# cc2538.net
KiCad netlist of a schematic drawn in Altium Designer
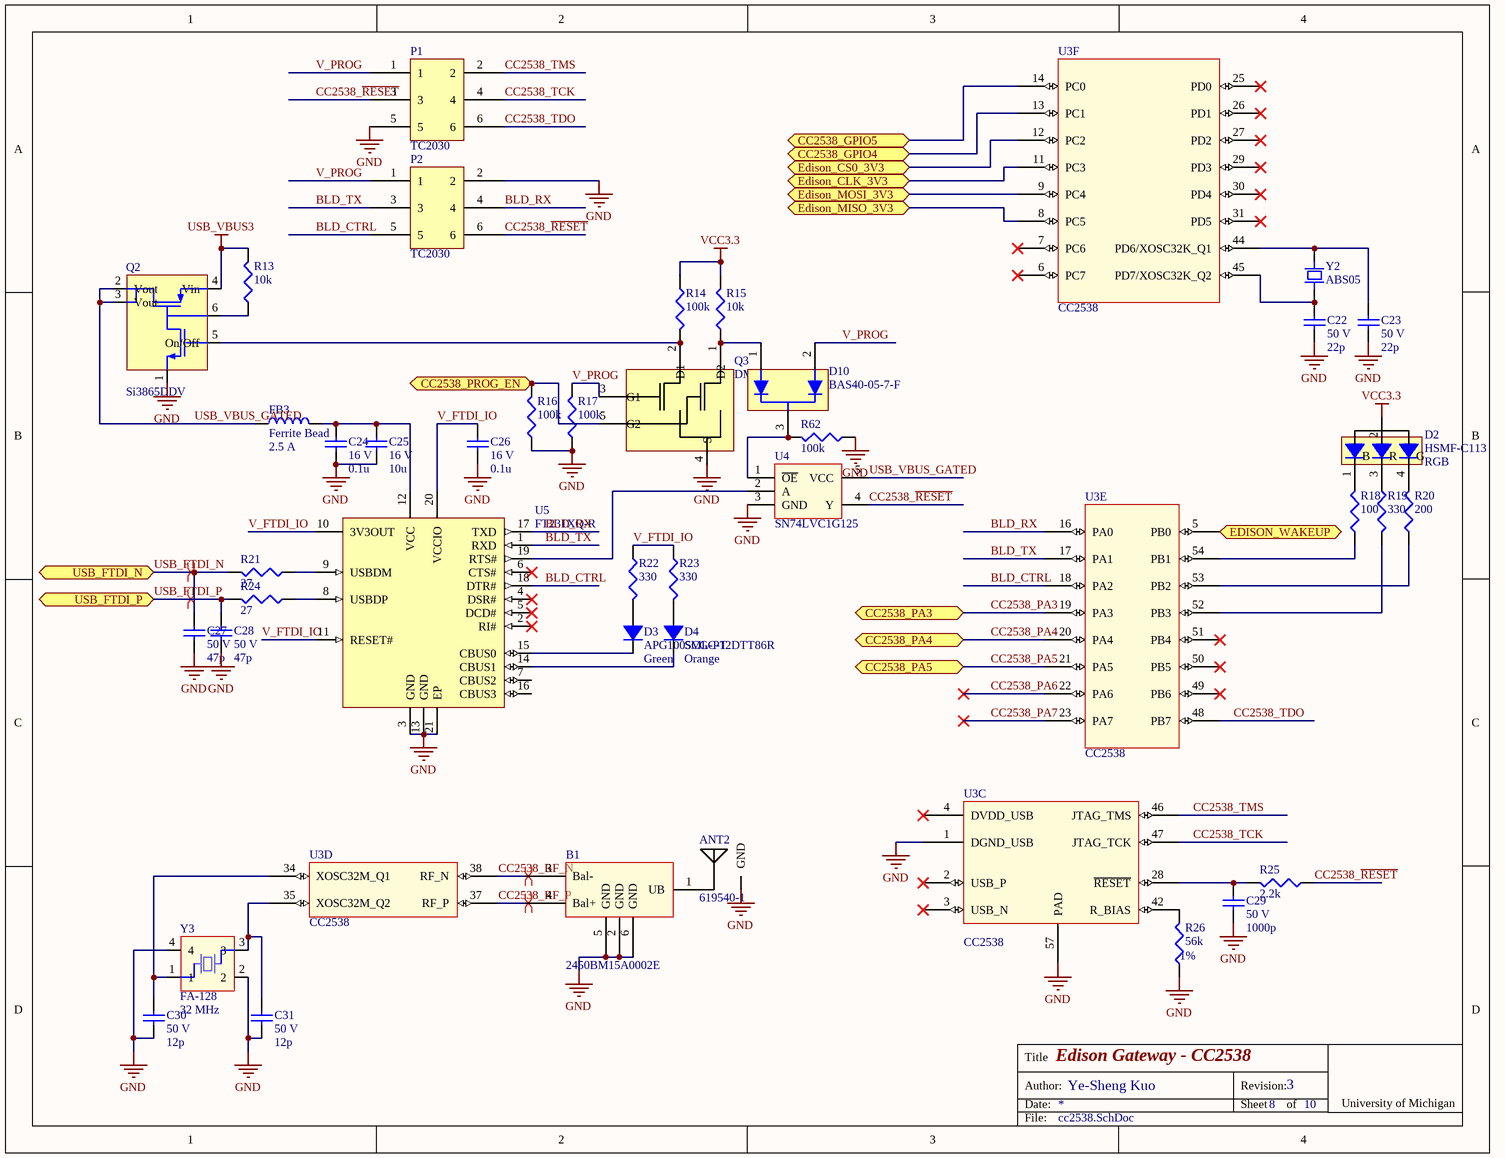
[diagram p0: cc2538.SchDoc]

(export (version "E")
  (design (tool "Eeschema 10.0.6"))
  (components
    (comp (ref "ANT2")
      (value "619540-1")
      (footprint "619540-1")
      (description "CONN SMA JACK")
      (libsource (lib "RF") (part "619540-1"))
    )
    (comp (ref "B1")
      (value "2450BM15A0002E")
      (footprint "2450BM15A0002")
      (description "2.45 GHz Balun for TI CC253X")
      (libsource (lib "RF") (part "2450BM15A0002E"))
    )
    (comp (ref "C22")
      (value "22p")
      (footprint "0402")
      (description "22pF ±2% 50V Ceramic Capacitor C0G, NP0 0402")
      (fields
        (field (name "VOLTAGE RATED") "50 V")
        (field (name "TOLERANCE") "2%")
        (field (name "MANUFACTURER PART NUMBER") "500R07S220GV4T")
      )
      (libsource (lib "capacitors") (part "500R07S220GV4T"))
    )
    (comp (ref "C23")
      (value "22p")
      (footprint "0402")
      (description "22pF ±2% 50V Ceramic Capacitor C0G, NP0 0402")
      (fields
        (field (name "VOLTAGE RATED") "50 V")
        (field (name "TOLERANCE") "2%")
        (field (name "MANUFACTURER PART NUMBER") "500R07S220GV4T")
      )
      (libsource (lib "capacitors") (part "500R07S220GV4T"))
    )
    (comp (ref "C24")
      (value "0.1u")
      (footprint "0402")
      (description "0.10µF ±10% 16V Ceramic Capacitor X7R 0402")
      (fields
        (field (name "TOLERANCE") "10%")
        (field (name "VOLTAGE RATED") "16 V")
        (field (name "MANUFACTURER PART NUMBER") "GRM155R71C104KA88D")
      )
      (libsource (lib "capacitors") (part "GRM155R71C104KA88D"))
    )
    (comp (ref "C25")
      (value "10u")
      (footprint "0603")
      (description "10µF ±20% 16V Ceramic Capacitor X6S 0603")
      (fields
        (field (name "TOLERANCE") "20%")
        (field (name "VOLTAGE RATED") "16 V")
        (field (name "MANUFACTURER PART NUMBER") "GRM188C81C106MA73D")
      )
      (libsource (lib "capacitors") (part "GRM188C81C106MA73D"))
    )
    (comp (ref "C26")
      (value "0.1u")
      (footprint "0402")
      (description "0.10µF ±10% 16V Ceramic Capacitor X7R 0402")
      (fields
        (field (name "TOLERANCE") "10%")
        (field (name "VOLTAGE RATED") "16 V")
        (field (name "MANUFACTURER PART NUMBER") "GRM155R71C104KA88D")
      )
      (libsource (lib "capacitors") (part "GRM155R71C104KA88D"))
    )
    (comp (ref "C27")
      (value "47p")
      (footprint "0402")
      (description "47pF ±5% 50V Ceramic Capacitor C0G, NP0 0402")
      (fields
        (field (name "TOLERANCE") "5%")
        (field (name "VOLTAGE RATED") "50 V")
        (field (name "MANUFACTURER PART NUMBER") "500R07N470JV4T")
      )
      (libsource (lib "capacitors") (part "500R07N470JV4T"))
    )
    (comp (ref "C28")
      (value "47p")
      (footprint "0402")
      (description "47pF ±5% 50V Ceramic Capacitor C0G, NP0 0402")
      (fields
        (field (name "TOLERANCE") "5%")
        (field (name "VOLTAGE RATED") "50 V")
        (field (name "MANUFACTURER PART NUMBER") "500R07N470JV4T")
      )
      (libsource (lib "capacitors") (part "500R07N470JV4T"))
    )
    (comp (ref "C29")
      (value "1000p")
      (footprint "0402")
      (description "1000pF ±5% 50V Ceramic Capacitor C0G, NP0 0402")
      (fields
        (field (name "VOLTAGE RATED") "50 V")
        (field (name "TOLERANCE") "5%")
        (field (name "MANUFACTURER PART NUMBER") "C1005C0G1H102J050BA")
      )
      (libsource (lib "capacitors") (part "C1005C0G1H102J050BA"))
    )
    (comp (ref "C30")
      (value "12p")
      (footprint "0402")
      (description "12pF ±2% 50V Ceramic Capacitor C0G, NP0 0402")
      (fields
        (field (name "VOLTAGE RATED") "50 V")
        (field (name "TOLERANCE") "2%")
        (field (name "MANUFACTURER PART NUMBER") "500R07S120GV4T")
      )
      (libsource (lib "capacitors") (part "500R07S120GV4T"))
    )
    (comp (ref "C31")
      (value "12p")
      (footprint "0402")
      (description "12pF ±2% 50V Ceramic Capacitor C0G, NP0 0402")
      (fields
        (field (name "VOLTAGE RATED") "50 V")
        (field (name "TOLERANCE") "2%")
        (field (name "MANUFACTURER PART NUMBER") "500R07S120GV4T")
      )
      (libsource (lib "capacitors") (part "500R07S120GV4T"))
    )
    (comp (ref "D2")
      (value "HSMF-C113")
      (footprint "HSMF")
      (fields (field (name "MANUFACTURER") "Broadcom Limited") (field (name "ALTIUM_VALUE") "RGB"))
      (libsource (lib "LED") (part "HSMF-C113"))
    )
    (comp (ref "D3")
      (value "APG1005CGC-T")
      (footprint "0402 - LED")
      (description "Green 571nm LED Indication - Discrete 2V 0402 (1005 Metric)")
      (fields (field (name "MANUFACTURER") "Kingbright") (field (name "ALTIUM_VALUE") "Green"))
      (libsource (lib "LED") (part "APG1005CGC-T"))
    )
    (comp (ref "D4")
      (value "SML-P12DTT86R")
      (footprint "0402 - LED")
      (description "Orange 605nm LED Indication - Discrete 2.1V 0402")
      (fields (field (name "MANUFACTURER") "Rohm Semiconductor") (field (name "ALTIUM_VALUE") "Orange"))
      (libsource (lib "LED") (part "SML-P12DTT86R"))
    )
    (comp (ref "D10")
      (value "BAS40-05-7-F")
      (footprint "SOT23-3")
      (description "Diode Array 1Pair Common Cathode Schottky 40V 200mA (DC) Surface Mount TO-236-3, SC-59, SOT-23-3")
      (fields (field (name "MANUFACTURER") "Diodes Incorporated"))
      (libsource (lib "diodes") (part "BAS40-05-7-F"))
    )
    (comp (ref "FB3")
      (value "Ferrite Bead")
      (footprint "0603")
      (description "FERRITE BEAD 220 OHM 0603")
      (fields
        (field (name "MANUFACTURER PART NUMBER") "BLM18SG221TN1D")
        (field (name "MANUFACTURER") "Murata")
        (field (name "CURRENT RATING (MAX)") "2.5 A")
      )
      (libsource (lib "ferrite_beads") (part "BLM18SG221TN1D"))
    )
    (comp (ref "P1")
      (value "TC2030")
      (footprint "TC2030-IDC-NLFP")
      (description "TC2030-MCP-NL")
      (libsource (lib "connectors") (part "TC2030"))
    )
    (comp (ref "P2")
      (value "TC2030")
      (footprint "TC2030-IDC-NLFP")
      (description "TC2030-MCP-NL")
      (libsource (lib "connectors") (part "TC2030"))
    )
    (comp (ref "Q2")
      (value "Si3865DDV")
      (footprint "TSOT-23")
      (description "Load Switch")
      (libsource (lib "load switch") (part "Si3865DDV"))
    )
    (comp (ref "Q3")
      (value "DMN32D2LDF")
      (footprint "SOT-353-5")
      (description "Common Source Dual N-Channel MOSFET")
      (libsource (lib "transistors") (part "DMN32D2LDF"))
    )
    (comp (ref "R13")
      (value "10k")
      (footprint "0402")
      (description "RES SMD 10K OHM 1% 1/16W 0402")
      (fields (field (name "TOLERANCE") "1%") (field (name "POWER") "1/16 W"))
      (libsource (lib "resistors") (part "CRCW040210K0FKED"))
    )
    (comp (ref "R14")
      (value "100k")
      (footprint "0402")
      (description "RES SMD 100K OHM 1% 1/16W 0402")
      (fields (field (name "TOLERANCE") "1%") (field (name "POWER") "1/16 W"))
      (libsource (lib "resistors") (part "CRCW0402100KFKED"))
    )
    (comp (ref "R15")
      (value "10k")
      (footprint "0402")
      (description "RES SMD 10K OHM 1% 1/16W 0402")
      (fields
        (field (name "MANUFACTURER PART NUMBER") "CRCW040210K0FKED")
        (field (name "MANUFACTURER") "Vishay Dale")
      )
      (libsource (lib "resistors") (part "CRCW040210K0FKED"))
    )
    (comp (ref "R16")
      (value "100k")
      (footprint "0402")
      (description "RES SMD 100K OHM 1% 1/16W 0402")
      (fields (field (name "TOLERANCE") "1%") (field (name "POWER") "1/16 W"))
      (libsource (lib "resistors") (part "CRCW0402100KFKED"))
    )
    (comp (ref "R17")
      (value "100k")
      (footprint "0402")
      (description "RES SMD 100K OHM 1% 1/16W 0402")
      (fields (field (name "TOLERANCE") "1%") (field (name "POWER") "1/16 W"))
      (libsource (lib "resistors") (part "CRCW0402100KFKED"))
    )
    (comp (ref "R18")
      (value "100")
      (footprint "0402")
      (description "RES SMD 100 OHM 1% 1/16W 0402")
      (fields (field (name "TOLERANCE") "1%") (field (name "POWER") "1/16 W"))
      (libsource (lib "resistors") (part "CRCW0402100RFKED"))
    )
    (comp (ref "R19")
      (value "330")
      (footprint "0402")
      (description "RES SMD 330 OHM 1% 1/16W 0402")
      (fields (field (name "TOLERANCE") "1%") (field (name "POWER") "1/16 W"))
      (libsource (lib "resistors") (part "CRCW0402330RFKED"))
    )
    (comp (ref "R20")
      (value "200")
      (footprint "0402")
      (description "RES SMD 200 OHM 1% 1/16W 0402")
      (fields (field (name "TOLERANCE") "1%") (field (name "POWER") "1/16 W"))
      (libsource (lib "resistors") (part "CRCW0402200RFKED"))
    )
    (comp (ref "R21")
      (value "27")
      (footprint "0402")
      (description "RES SMD 27 OHM 1% 1/16W 0402")
      (fields (field (name "TOLERANCE") "1%") (field (name "POWER") "1/16 W"))
      (libsource (lib "resistors") (part "CRCW040227R0FKED"))
    )
    (comp (ref "R22")
      (value "330")
      (footprint "0402")
      (description "RES SMD 330 OHM 1% 1/16W 0402")
      (fields (field (name "TOLERANCE") "1%") (field (name "POWER") "1/16 W"))
      (libsource (lib "resistors") (part "CRCW0402330RFKED"))
    )
    (comp (ref "R23")
      (value "330")
      (footprint "0402")
      (description "RES SMD 330 OHM 1% 1/16W 0402")
      (fields (field (name "TOLERANCE") "1%") (field (name "POWER") "1/16 W"))
      (libsource (lib "resistors") (part "CRCW0402330RFKED"))
    )
    (comp (ref "R24")
      (value "27")
      (footprint "0402")
      (description "RES SMD 27 OHM 1% 1/16W 0402")
      (fields (field (name "TOLERANCE") "1%") (field (name "POWER") "1/16 W"))
      (libsource (lib "resistors") (part "CRCW040227R0FKED"))
    )
    (comp (ref "R25")
      (value "2.2k")
      (footprint "0402")
      (description "RES SMD 2.2K OHM 1% 1/16W 0402")
      (fields (field (name "TOLERANCE") "1%") (field (name "POWER") "1/16 W"))
      (libsource (lib "resistors") (part "CRCW04022K20FKED"))
    )
    (comp (ref "R26")
      (value "56k")
      (footprint "0402")
      (description "RES SMD 56K OHM 1% 1/16W 0402")
      (fields
        (field (name "POWER") "1/16 W")
        (field (name "TOLERANCE") "1%")
        (field (name "MANUFACTURER PART NUMBER") "CRCW040256K0FKED")
      )
      (libsource (lib "resistors") (part "CRCW040256K0FKED"))
    )
    (comp (ref "R62")
      (value "100k")
      (footprint "0402")
      (description "RES SMD 100K OHM 1% 1/16W 0402")
      (fields
        (field (name "MANUFACTURER PART NUMBER") "CRCW0402100KFKED")
        (field (name "MANUFACTURER") "Vishay Dale")
      )
      (libsource (lib "resistors") (part "CRCW0402100KFKED"))
    )
    (comp (ref "U3")
      (value "CC2538")
      (footprint "QFN56")
      (description "A Powerful System-On-Chip for 2.4-GHz IEEE 802.15.4, 6LoWPAN  and ZigBee Applications")
      (libsource (lib "MCU") (part "CC2538"))
    )
    (comp (ref "U4")
      (value "SN74LVC1G125")
      (footprint "SOT23-5")
      (description "Single Bus Buffer Gate With 3-State Output")
      (libsource (lib "logics") (part "SN74LVC1G125"))
    )
    (comp (ref "U5")
      (value "FT231XQ-R")
      (footprint "QFN-20_N")
      (fields (field (name "MANUFACTURER") "FTDI"))
      (libsource (lib "FTDI FT-X Series") (part "FT231XQ-R"))
    )
    (comp (ref "Y2")
      (value "ABS05")
      (footprint "ABS05")
      (description "32768 Hz SMD Low profile crystal")
      (libsource (lib "crystal_oscillators_rtc") (part "ABS05"))
    )
    (comp (ref "Y3")
      (value "FA-128")
      (footprint "FA-128")
      (description "MHz Range Crystal Unit")
      (fields (field (name "FREQUENCY") "32 MHz"))
      (libsource (lib "crystal oscillators") (part "FA-128"))
    )
  )
  (nets
    (net (code "1") (name "/BLD_CTRL") (class "Default")
      (node (ref "P2") (pin "5") (pinfunction "5_5") (pintype "passive"))
      (node (ref "U3") (pin "18") (pinfunction "PA2_18") (pintype "bidirectional"))
      (node (ref "U5") (pin "18") (pinfunction "DTR#_18") (pintype "output"))
    )
    (net (code "2") (name "/BLD_RX") (class "Default")
      (node (ref "P2") (pin "4") (pinfunction "4_4") (pintype "passive"))
      (node (ref "U3") (pin "16") (pinfunction "PA0_16") (pintype "bidirectional"))
      (node (ref "U5") (pin "17") (pinfunction "TXD_17") (pintype "output"))
    )
    (net (code "3") (name "/BLD_TX") (class "Default")
      (node (ref "P2") (pin "3") (pinfunction "3_3") (pintype "passive"))
      (node (ref "U3") (pin "17") (pinfunction "PA1_17") (pintype "bidirectional"))
      (node (ref "U5") (pin "1") (pinfunction "RXD_1") (pintype "input"))
    )
    (net (code "4") (name "/CC2538_GPIO4") (class "Default")
      (node (ref "U3") (pin "13") (pinfunction "PC1_13") (pintype "bidirectional"))
    )
    (net (code "5") (name "/CC2538_GPIO5") (class "Default")
      (node (ref "U3") (pin "14") (pinfunction "PC0_14") (pintype "bidirectional"))
    )
    (net (code "6") (name "/CC2538_PA3") (class "Default")
      (node (ref "U3") (pin "19") (pinfunction "PA3_19") (pintype "bidirectional"))
    )
    (net (code "7") (name "/CC2538_PA4") (class "Default")
      (node (ref "U3") (pin "20") (pinfunction "PA4_20") (pintype "bidirectional"))
    )
    (net (code "8") (name "/CC2538_PA5") (class "Default")
      (node (ref "U3") (pin "21") (pinfunction "PA5_21") (pintype "bidirectional"))
    )
    (net (code "9") (name "/CC2538_PA6") (class "Default")
      (node (ref "U3") (pin "22") (pinfunction "PA6_22") (pintype "bidirectional+no_connect"))
    )
    (net (code "10") (name "/CC2538_PA7") (class "Default")
      (node (ref "U3") (pin "23") (pinfunction "PA7_23") (pintype "bidirectional+no_connect"))
    )
    (net (code "11") (name "/CC2538_PROG_EN") (class "Default")
      (node (ref "Q3") (pin "5") (pinfunction "G2_5") (pintype "passive"))
      (node (ref "R16") (pin "1") (pintype "passive"))
    )
    (net (code "12") (name "/CC2538_RF_N") (class "Default")
      (node (ref "B1") (pin "3") (pinfunction "Bal-_3") (pintype "passive"))
      (node (ref "U3") (pin "38") (pinfunction "RF_N_38") (pintype "bidirectional"))
    )
    (net (code "13") (name "/CC2538_RF_P") (class "Default")
      (node (ref "B1") (pin "4") (pinfunction "Bal+_4") (pintype "passive"))
      (node (ref "U3") (pin "37") (pinfunction "RF_P_37") (pintype "bidirectional"))
    )
    (net (code "14") (name "/CC2538_TCK") (class "Default")
      (node (ref "P1") (pin "4") (pinfunction "4_4") (pintype "passive"))
      (node (ref "U3") (pin "47") (pinfunction "JTAG_TCK_47") (pintype "bidirectional"))
    )
    (net (code "15") (name "/CC2538_TDO") (class "Default")
      (node (ref "P1") (pin "6") (pinfunction "6_6") (pintype "passive"))
      (node (ref "U3") (pin "48") (pinfunction "PB7_48") (pintype "bidirectional"))
    )
    (net (code "16") (name "/CC2538_TMS") (class "Default")
      (node (ref "P1") (pin "2") (pinfunction "2_2") (pintype "passive"))
      (node (ref "U3") (pin "46") (pinfunction "JTAG_TMS_46") (pintype "bidirectional"))
    )
    (net (code "17") (name "/CC2538_~{RESET}") (class "Default")
      (node (ref "P1") (pin "3") (pinfunction "3_3") (pintype "passive"))
      (node (ref "P2") (pin "6") (pinfunction "6_6") (pintype "passive"))
      (node (ref "R25") (pin "2") (pintype "passive"))
      (node (ref "U4") (pin "4") (pinfunction "Y_4") (pintype "passive"))
    )
    (net (code "18") (name "/EDISON_WAKEUP") (class "Default")
      (node (ref "U3") (pin "5") (pinfunction "PB0_5") (pintype "bidirectional"))
    )
    (net (code "19") (name "/Edison_CLK_3V3") (class "Default")
      (node (ref "U3") (pin "11") (pinfunction "PC3_11") (pintype "bidirectional"))
    )
    (net (code "20") (name "/Edison_CS0_3V3") (class "Default")
      (node (ref "U3") (pin "12") (pinfunction "PC2_12") (pintype "bidirectional"))
    )
    (net (code "21") (name "/Edison_MISO_3V3") (class "Default")
      (node (ref "U3") (pin "8") (pinfunction "PC5_8") (pintype "bidirectional"))
    )
    (net (code "22") (name "/Edison_MOSI_3V3") (class "Default")
      (node (ref "U3") (pin "9") (pinfunction "PC4_9") (pintype "bidirectional"))
    )
    (net (code "23") (name "/USB_FTDI_N") (class "Default")
      (node (ref "C27") (pin "2") (pintype "passive"))
      (node (ref "R21") (pin "1") (pintype "passive"))
    )
    (net (code "24") (name "/USB_FTDI_P") (class "Default")
      (node (ref "C28") (pin "2") (pintype "passive"))
      (node (ref "R24") (pin "1") (pintype "passive"))
    )
    (net (code "25") (name "/USB_VBUS_GATED") (class "Default")
      (node (ref "FB3") (pin "2") (pintype "passive"))
      (node (ref "Q2") (pin "2") (pinfunction "Vout_2") (pintype "passive"))
      (node (ref "Q2") (pin "3") (pinfunction "Vout_3") (pintype "passive"))
      (node (ref "U4") (pin "5") (pinfunction "VCC_5") (pintype "passive"))
    )
    (net (code "26") (name "/V_FTDI_IO") (class "Default")
      (node (ref "C26") (pin "1") (pintype "passive"))
      (node (ref "R22") (pin "2") (pintype "passive"))
      (node (ref "R23") (pin "2") (pintype "passive"))
      (node (ref "U5") (pin "10") (pinfunction "3V3OUT_10") (pintype "power_in"))
      (node (ref "U5") (pin "11") (pinfunction "RESET#_11") (pintype "input"))
      (node (ref "U5") (pin "20") (pinfunction "VCCIO_20") (pintype "power_in"))
    )
    (net (code "27") (name "/V_PROG") (class "Default")
      (node (ref "D10") (pin "2") (pinfunction "2_2") (pintype "passive"))
      (node (ref "P1") (pin "1") (pinfunction "1_1") (pintype "passive"))
      (node (ref "P2") (pin "1") (pinfunction "1_1") (pintype "passive"))
      (node (ref "Q3") (pin "3") (pinfunction "G1_3") (pintype "passive"))
      (node (ref "R17") (pin "1") (pintype "passive"))
    )
    (net (code "28") (name "GND") (class "Default")
      (node (ref "ANT2") (pin "1") (pinfunction "GND_1") (pintype "power_in"))
      (node (ref "B1") (pin "2") (pinfunction "GND_2") (pintype "passive"))
      (node (ref "B1") (pin "5") (pinfunction "GND_5") (pintype "passive"))
      (node (ref "B1") (pin "6") (pinfunction "GND_6") (pintype "passive"))
      (node (ref "C22") (pin "2") (pintype "passive"))
      (node (ref "C23") (pin "2") (pintype "passive"))
      (node (ref "C24") (pin "2") (pintype "passive"))
      (node (ref "C25") (pin "2") (pintype "passive"))
      (node (ref "C26") (pin "2") (pintype "passive"))
      (node (ref "C27") (pin "1") (pintype "passive"))
      (node (ref "C28") (pin "1") (pintype "passive"))
      (node (ref "C29") (pin "2") (pintype "passive"))
      (node (ref "C30") (pin "1") (pintype "passive"))
      (node (ref "C31") (pin "1") (pintype "passive"))
      (node (ref "P1") (pin "5") (pinfunction "5_5") (pintype "passive"))
      (node (ref "P2") (pin "2") (pinfunction "2_2") (pintype "passive"))
      (node (ref "Q2") (pin "1") (pintype "passive"))
      (node (ref "Q3") (pin "4") (pinfunction "S_4") (pintype "passive"))
      (node (ref "R16") (pin "2") (pintype "passive"))
      (node (ref "R17") (pin "2") (pintype "passive"))
      (node (ref "R26") (pin "2") (pintype "passive"))
      (node (ref "R62") (pin "2") (pintype "passive"))
      (node (ref "U3") (pin "1") (pinfunction "DGND_USB_1") (pintype "power_in"))
      (node (ref "U3") (pin "57") (pinfunction "PAD_57") (pintype "power_in"))
      (node (ref "U4") (pin "3") (pinfunction "GND_3") (pintype "passive"))
      (node (ref "U5") (pin "13") (pinfunction "GND_13") (pintype "power_in"))
      (node (ref "U5") (pin "21") (pinfunction "EP_21") (pintype "power_in"))
      (node (ref "U5") (pin "3") (pinfunction "GND_3") (pintype "power_in"))
      (node (ref "Y3") (pin "2") (pinfunction "2_2") (pintype "passive"))
      (node (ref "Y3") (pin "4") (pinfunction "4_4") (pintype "passive"))
    )
    (net (code "29") (name "Net-(B1-UB)") (class "Default")
      (node (ref "ANT2") (pin "2") (pintype "passive"))
      (node (ref "B1") (pin "1") (pinfunction "UB_1") (pintype "passive"))
    )
    (net (code "30") (name "Net-(D2-Pad1)") (class "Default")
      (node (ref "D2") (pin "1") (pintype "passive"))
      (node (ref "R18") (pin "1") (pintype "passive"))
    )
    (net (code "31") (name "Net-(D2-Pad3)") (class "Default")
      (node (ref "D2") (pin "3") (pinfunction "3_3") (pintype "passive"))
      (node (ref "R19") (pin "2") (pintype "passive"))
    )
    (net (code "32") (name "Net-(D2-Pad4)") (class "Default")
      (node (ref "D2") (pin "4") (pinfunction "4_4") (pintype "passive"))
      (node (ref "R20") (pin "1") (pintype "passive"))
    )
    (net (code "33") (name "Net-(D3-Pad1)") (class "Default")
      (node (ref "D3") (pin "1") (pintype "passive"))
      (node (ref "R22") (pin "1") (pintype "passive"))
    )
    (net (code "34") (name "Net-(D4-Pad1)") (class "Default")
      (node (ref "D4") (pin "1") (pintype "passive"))
      (node (ref "R23") (pin "1") (pintype "passive"))
    )
    (net (code "35") (name "Net-(Q2-On{slash}Off)") (class "Default")
      (node (ref "Q2") (pin "5") (pinfunction "On/Off_5") (pintype "passive"))
      (node (ref "Q3") (pin "2") (pinfunction "D1_2") (pintype "passive"))
      (node (ref "R14") (pin "2") (pintype "passive"))
    )
    (net (code "36") (name "Net-(Q2-Pad6)") (class "Default")
      (node (ref "Q2") (pin "6") (pintype "passive"))
      (node (ref "R13") (pin "2") (pintype "passive"))
    )
    (net (code "37") (name "Net-(Q3-D2)") (class "Default")
      (node (ref "D10") (pin "1") (pinfunction "1_1") (pintype "passive"))
      (node (ref "Q3") (pin "1") (pinfunction "D2_1") (pintype "passive"))
      (node (ref "R15") (pin "2") (pintype "passive"))
    )
    (net (code "38") (name "Net-(U3C-R_BIAS)") (class "Default")
      (node (ref "R26") (pin "1") (pintype "passive"))
      (node (ref "U3") (pin "42") (pinfunction "R_BIAS_42") (pintype "bidirectional"))
    )
    (net (code "39") (name "Net-(U3C-~{RESET})") (class "Default")
      (node (ref "C29") (pin "1") (pintype "passive"))
      (node (ref "R25") (pin "1") (pintype "passive"))
      (node (ref "U3") (pin "28") (pinfunction "~{RESET}_28") (pintype "bidirectional"))
    )
    (net (code "40") (name "Net-(U3D-XOSC32M_Q1)") (class "Default")
      (node (ref "C30") (pin "2") (pintype "passive"))
      (node (ref "U3") (pin "34") (pinfunction "XOSC32M_Q1_34") (pintype "bidirectional"))
      (node (ref "Y3") (pin "1") (pinfunction "1_1") (pintype "passive"))
    )
    (net (code "41") (name "Net-(U3D-XOSC32M_Q2)") (class "Default")
      (node (ref "C31") (pin "2") (pintype "passive"))
      (node (ref "U3") (pin "35") (pinfunction "XOSC32M_Q2_35") (pintype "bidirectional"))
      (node (ref "Y3") (pin "3") (pinfunction "3_3") (pintype "passive"))
    )
    (net (code "42") (name "Net-(U3E-PB1)") (class "Default")
      (node (ref "R18") (pin "2") (pintype "passive"))
      (node (ref "U3") (pin "54") (pinfunction "PB1_54") (pintype "bidirectional"))
    )
    (net (code "43") (name "Net-(U3E-PB2)") (class "Default")
      (node (ref "R20") (pin "2") (pintype "passive"))
      (node (ref "U3") (pin "53") (pinfunction "PB2_53") (pintype "bidirectional"))
    )
    (net (code "44") (name "Net-(U3E-PB3)") (class "Default")
      (node (ref "R19") (pin "1") (pintype "passive"))
      (node (ref "U3") (pin "52") (pinfunction "PB3_52") (pintype "bidirectional"))
    )
    (net (code "45") (name "Net-(U3F-PD6{slash}XOSC32K_Q1)") (class "Default")
      (node (ref "C23") (pin "1") (pintype "passive"))
      (node (ref "U3") (pin "44") (pinfunction "PD6/XOSC32K_Q1_44") (pintype "bidirectional"))
      (node (ref "Y2") (pin "1") (pintype "passive"))
    )
    (net (code "46") (name "Net-(U3F-PD7{slash}XOSC32K_Q2)") (class "Default")
      (node (ref "C22") (pin "1") (pintype "passive"))
      (node (ref "U3") (pin "45") (pinfunction "PD7/XOSC32K_Q2_45") (pintype "bidirectional"))
      (node (ref "Y2") (pin "2") (pintype "passive"))
    )
    (net (code "47") (name "Net-(U4-A)") (class "Default")
      (node (ref "U4") (pin "2") (pinfunction "A_2") (pintype "passive"))
      (node (ref "U5") (pin "19") (pinfunction "RTS#_19") (pintype "output"))
    )
    (net (code "48") (name "Net-(U4-~{OE})") (class "Default")
      (node (ref "D10") (pin "3") (pinfunction "3_3") (pintype "passive"))
      (node (ref "R62") (pin "1") (pintype "passive"))
      (node (ref "U4") (pin "1") (pinfunction "~{OE}_1") (pintype "passive"))
    )
    (net (code "49") (name "Net-(U5-CBUS0)") (class "Default")
      (node (ref "D3") (pin "2") (pintype "passive"))
      (node (ref "U5") (pin "15") (pinfunction "CBUS0_15") (pintype "bidirectional"))
    )
    (net (code "50") (name "Net-(U5-CBUS1)") (class "Default")
      (node (ref "D4") (pin "2") (pintype "passive"))
      (node (ref "U5") (pin "14") (pinfunction "CBUS1_14") (pintype "bidirectional"))
    )
    (net (code "51") (name "Net-(U5-USBDM)") (class "Default")
      (node (ref "R21") (pin "2") (pintype "passive"))
      (node (ref "U5") (pin "9") (pinfunction "USBDM_9") (pintype "input"))
    )
    (net (code "52") (name "Net-(U5-USBDP)") (class "Default")
      (node (ref "R24") (pin "2") (pintype "passive"))
      (node (ref "U5") (pin "8") (pinfunction "USBDP_8") (pintype "input"))
    )
    (net (code "53") (name "Net-(U5-VCC)") (class "Default")
      (node (ref "C24") (pin "1") (pintype "passive"))
      (node (ref "C25") (pin "1") (pintype "passive"))
      (node (ref "FB3") (pin "1") (pintype "passive"))
      (node (ref "U5") (pin "12") (pinfunction "VCC_12") (pintype "power_in"))
    )
    (net (code "54") (name "USB_VBUS3") (class "Default")
      (node (ref "Q2") (pin "4") (pinfunction "Vin_4") (pintype "passive"))
      (node (ref "R13") (pin "1") (pintype "passive"))
    )
    (net (code "55") (name "VCC3.3") (class "Default")
      (node (ref "D2") (pin "2") (pintype "passive"))
      (node (ref "R14") (pin "1") (pintype "passive"))
      (node (ref "R15") (pin "1") (pintype "passive"))
    )
    (net (code "56") (name "unconnected-(U3C-DVDD_USB-Pad4)") (class "Default")
      (node (ref "U3") (pin "4") (pinfunction "DVDD_USB_4") (pintype "power_in+no_connect"))
    )
    (net (code "57") (name "unconnected-(U3C-USB_N-Pad3)") (class "Default")
      (node (ref "U3") (pin "3") (pinfunction "USB_N_3") (pintype "bidirectional+no_connect"))
    )
    (net (code "58") (name "unconnected-(U3C-USB_P-Pad2)") (class "Default")
      (node (ref "U3") (pin "2") (pinfunction "USB_P_2") (pintype "bidirectional+no_connect"))
    )
    (net (code "59") (name "unconnected-(U3E-PB4-Pad51)") (class "Default")
      (node (ref "U3") (pin "51") (pinfunction "PB4_51") (pintype "bidirectional+no_connect"))
    )
    (net (code "60") (name "unconnected-(U3E-PB5-Pad50)") (class "Default")
      (node (ref "U3") (pin "50") (pinfunction "PB5_50") (pintype "bidirectional+no_connect"))
    )
    (net (code "61") (name "unconnected-(U3E-PB6-Pad49)") (class "Default")
      (node (ref "U3") (pin "49") (pinfunction "PB6_49") (pintype "bidirectional+no_connect"))
    )
    (net (code "62") (name "unconnected-(U3F-PC6-Pad7)") (class "Default")
      (node (ref "U3") (pin "7") (pinfunction "PC6_7") (pintype "bidirectional+no_connect"))
    )
    (net (code "63") (name "unconnected-(U3F-PC7-Pad6)") (class "Default")
      (node (ref "U3") (pin "6") (pinfunction "PC7_6") (pintype "bidirectional+no_connect"))
    )
    (net (code "64") (name "unconnected-(U3F-PD0-Pad25)") (class "Default")
      (node (ref "U3") (pin "25") (pinfunction "PD0_25") (pintype "bidirectional+no_connect"))
    )
    (net (code "65") (name "unconnected-(U3F-PD1-Pad26)") (class "Default")
      (node (ref "U3") (pin "26") (pinfunction "PD1_26") (pintype "bidirectional+no_connect"))
    )
    (net (code "66") (name "unconnected-(U3F-PD2-Pad27)") (class "Default")
      (node (ref "U3") (pin "27") (pinfunction "PD2_27") (pintype "bidirectional+no_connect"))
    )
    (net (code "67") (name "unconnected-(U3F-PD3-Pad29)") (class "Default")
      (node (ref "U3") (pin "29") (pinfunction "PD3_29") (pintype "bidirectional+no_connect"))
    )
    (net (code "68") (name "unconnected-(U3F-PD4-Pad30)") (class "Default")
      (node (ref "U3") (pin "30") (pinfunction "PD4_30") (pintype "bidirectional+no_connect"))
    )
    (net (code "69") (name "unconnected-(U3F-PD5-Pad31)") (class "Default")
      (node (ref "U3") (pin "31") (pinfunction "PD5_31") (pintype "bidirectional+no_connect"))
    )
    (net (code "70") (name "unconnected-(U5-CBUS2-Pad7)") (class "Default")
      (node (ref "U5") (pin "7") (pinfunction "CBUS2_7") (pintype "bidirectional"))
    )
    (net (code "71") (name "unconnected-(U5-CBUS3-Pad16)") (class "Default")
      (node (ref "U5") (pin "16") (pinfunction "CBUS3_16") (pintype "bidirectional"))
    )
    (net (code "72") (name "unconnected-(U5-CTS#-Pad6)") (class "Default")
      (node (ref "U5") (pin "6") (pinfunction "CTS#_6") (pintype "input+no_connect"))
    )
    (net (code "73") (name "unconnected-(U5-DCD#-Pad5)") (class "Default")
      (node (ref "U5") (pin "5") (pinfunction "DCD#_5") (pintype "input+no_connect"))
    )
    (net (code "74") (name "unconnected-(U5-DSR#-Pad4)") (class "Default")
      (node (ref "U5") (pin "4") (pinfunction "DSR#_4") (pintype "input+no_connect"))
    )
    (net (code "75") (name "unconnected-(U5-RI#-Pad2)") (class "Default")
      (node (ref "U5") (pin "2") (pinfunction "RI#_2") (pintype "input+no_connect"))
    )
  )
)
